# Supply.net
KiCad netlist of a schematic drawn in Altium Designer
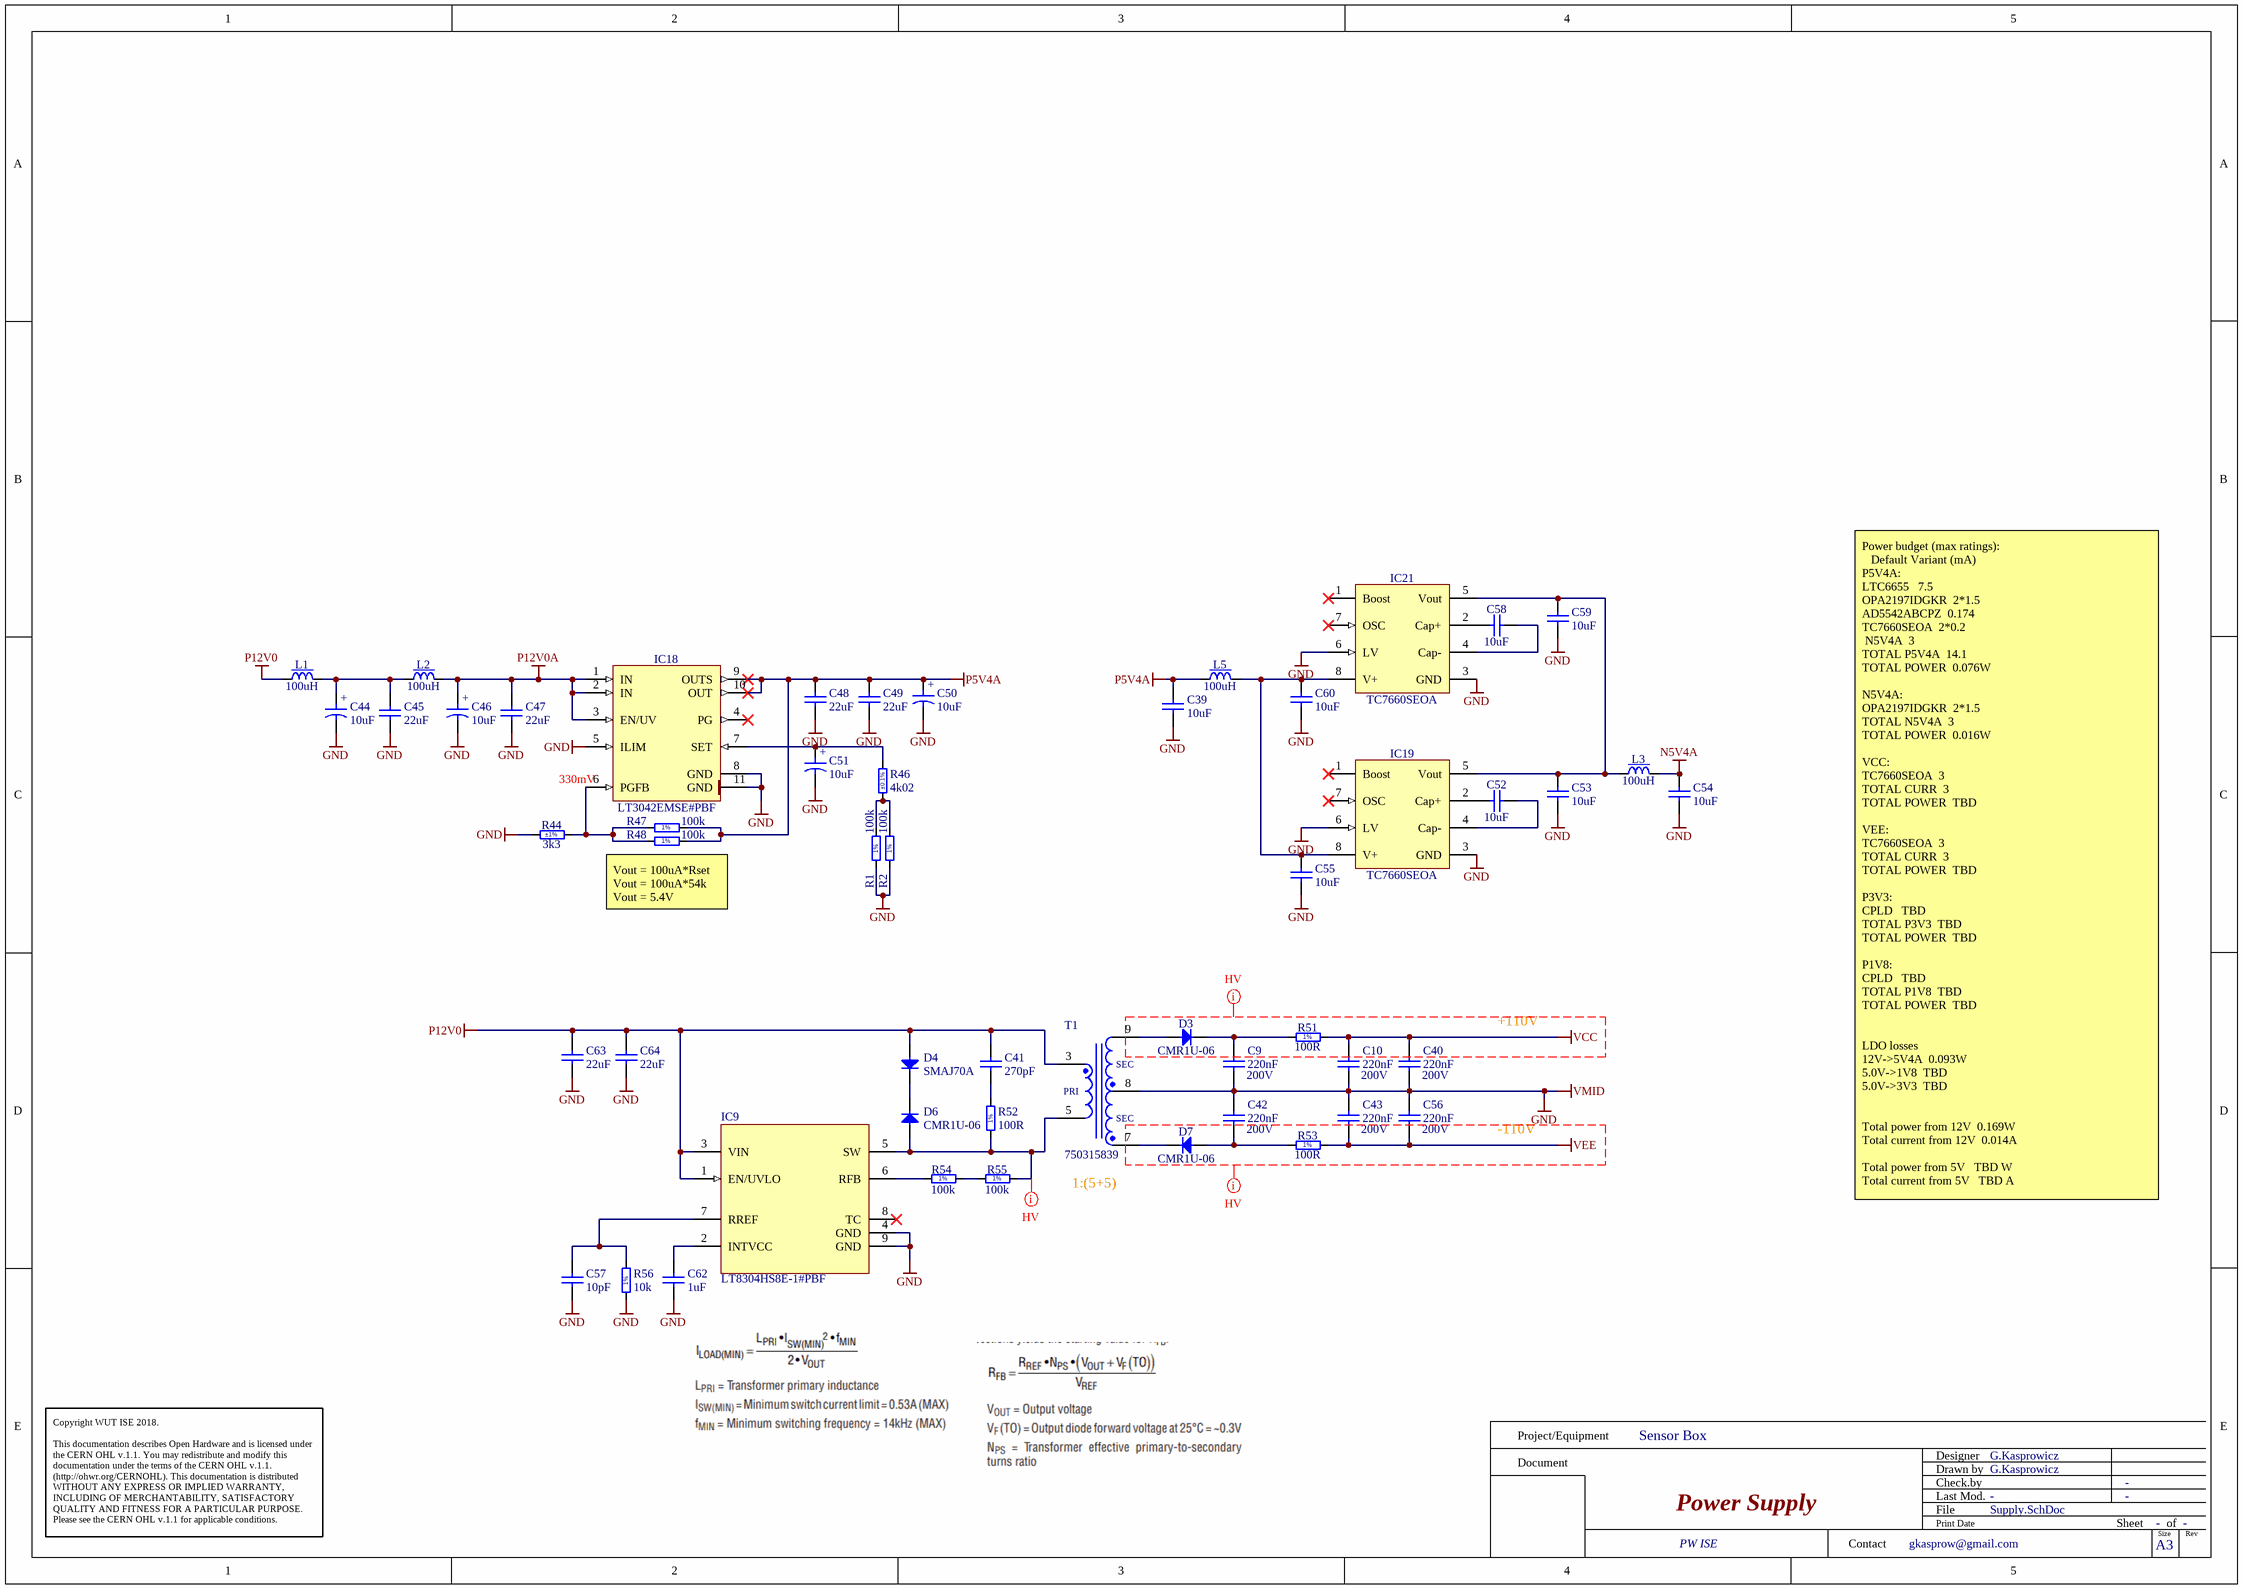
[diagram p0: Supply.SchDoc]

(export (version "E")
  (design (tool "Eeschema 10.0.6"))
  (components
    (comp (ref "C9")
      (value "220nF")
      (footprint "CAPC3216X140N")
      (description "Non-polarised capacitor")
      (fields
        (field (name "PART NUMBER") "CC1206_220NF_250V_10%_X7R")
        (field (name "TOLERANCE") "±10%")
        (field (name "VOLTAGE") "200V")
        (field (name "AUTHOR") "CERN DEM JLC")
      )
      (libsource (lib "Sensor-Box_ADHV") (part "CC1206_220NF_250V_10%_X7R"))
    )
    (comp (ref "C10")
      (value "220nF")
      (footprint "CAPC3216X140N")
      (description "Non-polarised capacitor")
      (fields
        (field (name "PART NUMBER") "CC1206_220NF_250V_10%_X7R")
        (field (name "TOLERANCE") "±10%")
        (field (name "VOLTAGE") "200V")
        (field (name "AUTHOR") "CERN DEM JLC")
      )
      (libsource (lib "Sensor-Box_ADHV") (part "CC1206_220NF_250V_10%_X7R"))
    )
    (comp (ref "C39")
      (value "10uF")
      (footprint "CAPC1608X80N")
      (description "Non-polarised capacitor")
      (fields
        (field (name "PART NUMBER") "CC0603_10UF_10V_10%_X5R")
        (field (name "VOLTAGE") "10V")
        (field (name "AUTHOR") "CERN DEM JLC")
      )
      (libsource (lib "Capacitors") (part "Capacitor - non polarized"))
    )
    (comp (ref "C40")
      (value "220nF")
      (footprint "CAPC3216X140N")
      (description "Non-polarised capacitor")
      (fields
        (field (name "PART NUMBER") "CC1206_220NF_250V_10%_X7R")
        (field (name "TOLERANCE") "±10%")
        (field (name "VOLTAGE") "200V")
        (field (name "AUTHOR") "CERN DEM JLC")
      )
      (libsource (lib "Sensor-Box_ADHV") (part "CC1206_220NF_250V_10%_X7R"))
    )
    (comp (ref "C41")
      (value "270pF")
      (footprint "CAPC2013X115N")
      (description "Non-polarised capacitor")
      (fields
        (field (name "PART NUMBER") "CC0805_270PF_100V_5%_C0G")
        (field (name "VOLTAGE") "100V")
        (field (name "AUTHOR") "CERN DEM JLC")
      )
      (libsource (lib "Sensor-Box_ADHV") (part "CC0805_270PF_100V_5%_C0G"))
    )
    (comp (ref "C42")
      (value "220nF")
      (footprint "CAPC3216X140N")
      (description "Non-polarised capacitor")
      (fields
        (field (name "PART NUMBER") "CC1206_220NF_250V_10%_X7R")
        (field (name "TOLERANCE") "±10%")
        (field (name "VOLTAGE") "200V")
        (field (name "AUTHOR") "CERN DEM JLC")
      )
      (libsource (lib "Sensor-Box_ADHV") (part "CC1206_220NF_250V_10%_X7R"))
    )
    (comp (ref "C43")
      (value "220nF")
      (footprint "CAPC3216X140N")
      (description "Non-polarised capacitor")
      (fields
        (field (name "PART NUMBER") "CC1206_220NF_250V_10%_X7R")
        (field (name "TOLERANCE") "±10%")
        (field (name "VOLTAGE") "200V")
        (field (name "AUTHOR") "CERN DEM JLC")
      )
      (libsource (lib "Sensor-Box_ADHV") (part "CC1206_220NF_250V_10%_X7R"))
    )
    (comp (ref "C44")
      (value "10uF")
      (footprint "CAPMP3216X180N")
      (description "Polarised capacitor")
      (fields
        (field (name "PART NUMBER") "CTE3216-18_10UF_16V_20%_AVX_TCJ")
        (field (name "VOLTAGE") "16V")
        (field (name "AUTHOR") "CERN DEM JLC")
      )
      (libsource (lib "Capacitors") (part "Capacitor - polarized"))
    )
    (comp (ref "C45")
      (value "22uF")
      (footprint "CAPC2012X135N")
      (description "Non-polarised capacitor")
      (fields
        (field (name "PART NUMBER") "CC0805_22UF_16V_10%_X5R")
        (field (name "VOLTAGE") "16V")
        (field (name "AUTHOR") "CERN DEM JLC")
      )
      (libsource (lib "Capacitors") (part "Capacitor - non polarized"))
    )
    (comp (ref "C46")
      (value "10uF")
      (footprint "CAPMP3216X180N")
      (description "Polarised capacitor")
      (fields
        (field (name "PART NUMBER") "CTE3216-18_10UF_16V_20%_AVX_TCJ")
        (field (name "VOLTAGE") "16V")
        (field (name "AUTHOR") "CERN DEM JLC")
      )
      (libsource (lib "Capacitors") (part "Capacitor - polarized"))
    )
    (comp (ref "C47")
      (value "22uF")
      (footprint "CAPC2012X135N")
      (description "Non-polarised capacitor")
      (fields
        (field (name "PART NUMBER") "CC0805_22UF_16V_10%_X5R")
        (field (name "VOLTAGE") "16V")
        (field (name "AUTHOR") "CERN DEM JLC")
      )
      (libsource (lib "Capacitors") (part "Capacitor - non polarized"))
    )
    (comp (ref "C48")
      (value "22uF")
      (footprint "CAPC2012X135N")
      (description "Non-polarised capacitor")
      (fields
        (field (name "PART NUMBER") "CC0805_22UF_16V_10%_X5R")
        (field (name "VOLTAGE") "16V")
        (field (name "AUTHOR") "CERN DEM JLC")
      )
      (libsource (lib "Capacitors") (part "Capacitor - non polarized"))
    )
    (comp (ref "C49")
      (value "22uF")
      (footprint "CAPC2012X135N")
      (description "Non-polarised capacitor")
      (fields
        (field (name "PART NUMBER") "CC0805_22UF_16V_10%_X5R")
        (field (name "VOLTAGE") "16V")
        (field (name "AUTHOR") "CERN DEM JLC")
      )
      (libsource (lib "Capacitors") (part "Capacitor - non polarized"))
    )
    (comp (ref "C50")
      (value "10uF")
      (footprint "CAPMP3216X180N")
      (description "Polarised capacitor")
      (fields
        (field (name "PART NUMBER") "CTE3216-18_10UF_16V_20%_AVX_TCJ")
        (field (name "VOLTAGE") "16V")
        (field (name "AUTHOR") "CERN DEM JLC")
      )
      (libsource (lib "Capacitors") (part "Capacitor - polarized"))
    )
    (comp (ref "C51")
      (value "10uF")
      (footprint "CAPMP3216X180N")
      (description "Polarised capacitor")
      (fields
        (field (name "PART NUMBER") "CTE3216-18_10UF_16V_20%_AVX_TCJ")
        (field (name "VOLTAGE") "16V")
        (field (name "AUTHOR") "CERN DEM JLC")
      )
      (libsource (lib "Capacitors") (part "Capacitor - polarized"))
    )
    (comp (ref "C52")
      (value "10uF")
      (footprint "CAPC1608X80N")
      (description "Non-polarised capacitor")
      (fields
        (field (name "PART NUMBER") "CC0603_10UF_10V_10%_X5R")
        (field (name "VOLTAGE") "10V")
        (field (name "AUTHOR") "CERN DEM JLC")
      )
      (libsource (lib "Capacitors") (part "Capacitor - non polarized"))
    )
    (comp (ref "C53")
      (value "10uF")
      (footprint "CAPC1608X80N")
      (description "Non-polarised capacitor")
      (fields
        (field (name "PART NUMBER") "CC0603_10UF_10V_10%_X5R")
        (field (name "VOLTAGE") "10V")
        (field (name "AUTHOR") "CERN DEM JLC")
      )
      (libsource (lib "Capacitors") (part "Capacitor - non polarized"))
    )
    (comp (ref "C54")
      (value "10uF")
      (footprint "CAPC1608X80N")
      (description "Non-polarised capacitor")
      (fields
        (field (name "PART NUMBER") "CC0603_10UF_10V_10%_X5R")
        (field (name "VOLTAGE") "10V")
        (field (name "AUTHOR") "CERN DEM JLC")
      )
      (libsource (lib "Capacitors") (part "Capacitor - non polarized"))
    )
    (comp (ref "C55")
      (value "10uF")
      (footprint "CAPC1608X80N")
      (description "Non-polarised capacitor")
      (fields
        (field (name "PART NUMBER") "CC0603_10UF_10V_10%_X5R")
        (field (name "VOLTAGE") "10V")
        (field (name "AUTHOR") "CERN DEM JLC")
      )
      (libsource (lib "Capacitors") (part "Capacitor - non polarized"))
    )
    (comp (ref "C56")
      (value "220nF")
      (footprint "CAPC3216X140N")
      (description "Non-polarised capacitor")
      (fields
        (field (name "PART NUMBER") "CC1206_220NF_250V_10%_X7R")
        (field (name "TOLERANCE") "±10%")
        (field (name "VOLTAGE") "200V")
        (field (name "AUTHOR") "CERN DEM JLC")
      )
      (libsource (lib "Sensor-Box_ADHV") (part "CC1206_220NF_250V_10%_X7R"))
    )
    (comp (ref "C57")
      (value "10pF")
      (footprint "CAPC1005X55N")
      (description "Non-polarised capacitor")
      (fields
        (field (name "PART NUMBER") "CC0402_10PF_50V_5%_C0G")
        (field (name "VOLTAGE") "50V")
        (field (name "AUTHOR") "CERN DEM JLC")
      )
      (libsource (lib "Sensor-Box_ADHV") (part "CC0402_10PF_50V_5%_C0G"))
    )
    (comp (ref "C58")
      (value "10uF")
      (footprint "CAPC1608X80N")
      (description "Non-polarised capacitor")
      (fields
        (field (name "PART NUMBER") "CC0603_10UF_10V_10%_X5R")
        (field (name "VOLTAGE") "10V")
        (field (name "AUTHOR") "CERN DEM JLC")
      )
      (libsource (lib "Capacitors") (part "Capacitor - non polarized"))
    )
    (comp (ref "C59")
      (value "10uF")
      (footprint "CAPC1608X80N")
      (description "Non-polarised capacitor")
      (fields
        (field (name "PART NUMBER") "CC0603_10UF_10V_10%_X5R")
        (field (name "VOLTAGE") "10V")
        (field (name "AUTHOR") "CERN DEM JLC")
      )
      (libsource (lib "Capacitors") (part "Capacitor - non polarized"))
    )
    (comp (ref "C60")
      (value "10uF")
      (footprint "CAPC1608X80N")
      (description "Non-polarised capacitor")
      (fields
        (field (name "PART NUMBER") "CC0603_10UF_10V_10%_X5R")
        (field (name "VOLTAGE") "10V")
        (field (name "AUTHOR") "CERN DEM JLC")
      )
      (libsource (lib "Capacitors") (part "Capacitor - non polarized"))
    )
    (comp (ref "C62")
      (value "1uF")
      (footprint "CAPC1608X87N")
      (description "Non-polarised capacitor")
      (fields
        (field (name "PART NUMBER") "CC0603_1UF_25V_10%_X7R")
        (field (name "VOLTAGE") "25V")
        (field (name "AUTHOR") "CERN DEM JLC")
      )
      (libsource (lib "Capacitors") (part "Capacitor - non polarized"))
    )
    (comp (ref "C63")
      (value "22uF")
      (footprint "CAPC2012X135N")
      (description "Non-polarised capacitor")
      (fields
        (field (name "PART NUMBER") "CC0805_22UF_16V_10%_X5R")
        (field (name "VOLTAGE") "16V")
        (field (name "AUTHOR") "CERN DEM JLC")
      )
      (libsource (lib "Capacitors") (part "Capacitor - non polarized"))
    )
    (comp (ref "C64")
      (value "22uF")
      (footprint "CAPC2012X135N")
      (description "Non-polarised capacitor")
      (fields
        (field (name "PART NUMBER") "CC0805_22UF_16V_10%_X5R")
        (field (name "VOLTAGE") "16V")
        (field (name "AUTHOR") "CERN DEM JLC")
      )
      (libsource (lib "Capacitors") (part "Capacitor - non polarized"))
    )
    (comp (ref "D3")
      (value "CMR1U-06")
      (footprint "FP-SMA-MFG")
      (description "Diode")
      (fields
        (field (name "VOLTAGE") "600V")
        (field (name "MANUFACTURER") "Central Semiconductor")
        (field (name "AUTHOR") "CERN DEM JLC")
      )
      (libsource (lib "Sensor-Box_ADHV") (part "CMR1U-06"))
    )
    (comp (ref "D4")
      (value "SMAJ70A")
      (footprint "FP-SMA-MFG")
      (description "Diode")
      (fields
        (field (name "VOLTAGE") "70V")
        (field (name "POWER") "400W")
        (field (name "AUTHOR") "CERN DEM JLC")
      )
      (libsource (lib "Sensor-Box_ADHV") (part "SMAJ70A"))
    )
    (comp (ref "D6")
      (value "CMR1U-06")
      (footprint "FP-SMA-MFG")
      (description "Diode")
      (fields
        (field (name "VOLTAGE") "600V")
        (field (name "MANUFACTURER") "Central Semiconductor")
        (field (name "AUTHOR") "CERN DEM JLC")
      )
      (libsource (lib "Sensor-Box_ADHV") (part "CMR1U-06"))
    )
    (comp (ref "D7")
      (value "CMR1U-06")
      (footprint "FP-SMA-MFG")
      (description "Diode")
      (fields
        (field (name "VOLTAGE") "600V")
        (field (name "MANUFACTURER") "Central Semiconductor")
        (field (name "AUTHOR") "CERN DEM JLC")
      )
      (libsource (lib "Sensor-Box_ADHV") (part "CMR1U-06"))
    )
    (comp (ref "IC9")
      (value "LT8304HS8E-1#PBF")
      (footprint "FP-S8E-8-05-08-1857-MFG")
      (description "IC REG FLYBACK ADJ 2A 8SOIC")
      (fields (field (name "MANUFACTURER") "Analog Devices"))
      (libsource (lib "Sensor-Box_ADHV") (part "LT8304HS8E-1#PBF"))
    )
    (comp (ref "IC18")
      (value "LT3042EMSE#PBF")
      (footprint "SOP50P490X110-11N-R168X198")
      (description "20V, 200mA, Ultralow Noise, Ultrahigh PSRR RF Linear Regulator")
      (fields (field (name "MANUFACTURER") "LINEAR TECHNOLOGY") (field (name "AUTHOR") "CERN DEM MR"))
      (libsource (lib "ICs And Semiconductors") (part "LT3042"))
    )
    (comp (ref "IC19")
      (value "TC7660SEOA")
      (footprint "SOIC127P600X175-8N")
      (description "Super Charge Pump DC-to-DC Voltage Converter")
      (fields (field (name "MANUFACTURER") "MICROCHIP TECHNOLOGY") (field (name "AUTHOR") "CERN DEM HF"))
      (libsource (lib "ICs And Semiconductors") (part "TC7660S"))
    )
    (comp (ref "IC21")
      (value "TC7660SEOA")
      (footprint "SOIC127P600X175-8N")
      (description "Super Charge Pump DC-to-DC Voltage Converter")
      (fields (field (name "MANUFACTURER") "MICROCHIP TECHNOLOGY") (field (name "AUTHOR") "CERN DEM HF"))
      (libsource (lib "ICs And Semiconductors") (part "TC7660S"))
    )
    (comp (ref "L1")
      (value "100uH")
      (footprint "INDM5650X530N")
      (description "Inductor With Core")
      (fields
        (field (name "PART NUMBER") "IND2220_100UH_10%_EPCOS_B82442H")
        (field (name "POWER") "350mA")
        (field (name "AUTHOR") "CERN DEM JLC")
      )
      (libsource (lib "Inductors & Transformers") (part "Inductor With Magnetic core"))
    )
    (comp (ref "L2")
      (value "100uH")
      (footprint "INDM5650X530N")
      (description "Inductor With Core")
      (fields
        (field (name "PART NUMBER") "IND2220_100UH_10%_EPCOS_B82442H")
        (field (name "POWER") "350mA")
        (field (name "AUTHOR") "CERN DEM JLC")
      )
      (libsource (lib "Inductors & Transformers") (part "Inductor With Magnetic core"))
    )
    (comp (ref "L3")
      (value "100uH")
      (footprint "INDM3225X240N")
      (description "Inductor With Core")
      (fields
        (field (name "PART NUMBER") "IND1210_100UH_10%_EPCOS_B82422H")
        (field (name "POWER") "150mA")
        (field (name "AUTHOR") "CERN DEM JLC")
      )
      (libsource (lib "Inductors & Transformers") (part "Inductor With Magnetic core"))
    )
    (comp (ref "L5")
      (value "100uH")
      (footprint "INDM3225X240N")
      (description "Inductor With Core")
      (fields
        (field (name "PART NUMBER") "IND1210_100UH_10%_EPCOS_B82422H")
        (field (name "POWER") "150mA")
        (field (name "AUTHOR") "CERN DEM JLC")
      )
      (libsource (lib "Inductors & Transformers") (part "Inductor With Magnetic core"))
    )
    (comp (ref "R1")
      (value "100k")
      (footprint "RESC1005X40N")
      (description "Resistor - 1%")
      (fields
        (field (name "PART NUMBER") "R0402_100K_1%_0.0625W_100PPM")
        (field (name "MANUFACTURER") "GENERIC")
        (field (name "AUTHOR") "CERN DEM JLC")
      )
      (libsource (lib "Resistors") (part "Resistor - 1%"))
    )
    (comp (ref "R2")
      (value "100k")
      (footprint "RESC1005X40N")
      (description "Resistor - 1%")
      (fields
        (field (name "PART NUMBER") "R0402_100K_1%_0.0625W_100PPM")
        (field (name "MANUFACTURER") "GENERIC")
        (field (name "AUTHOR") "CERN DEM JLC")
      )
      (libsource (lib "Resistors") (part "Resistor - 1%"))
    )
    (comp (ref "R44")
      (value "3k3")
      (footprint "RESC1005X40N")
      (description "Resistor - 1%")
      (fields
        (field (name "TOLERANCE") "±1%")
        (field (name "PART NUMBER") "R0402_3K3_1%_0.0625W_100PPM")
        (field (name "POWER") "0.0625W")
        (field (name "AUTHOR") "CERN DEM JLC")
      )
      (libsource (lib "Resistors") (part "Resistor - 1%"))
    )
    (comp (ref "R46")
      (value "4k02")
      (footprint "RESC1608X55N")
      (description "Resistor - 0.1%")
      (fields
        (field (name "PART NUMBER") "R0603_4K02_0.1%_0.063W_10PPM")
        (field (name "POWER") "0.063W")
        (field (name "TOLERANCE") "±0.1%")
        (field (name "AUTHOR") "CERN DEM BC")
      )
      (libsource (lib "Sensor-Box_Piezo_Driver") (part "R0603_4K02_0.1%_0.063W_10PPM_1"))
    )
    (comp (ref "R47")
      (value "100k")
      (footprint "RESC1005X40N")
      (description "Resistor - 1%")
      (fields
        (field (name "PART NUMBER") "R0402_100K_1%_0.0625W_100PPM")
        (field (name "MANUFACTURER") "GENERIC")
        (field (name "AUTHOR") "CERN DEM JLC")
      )
      (libsource (lib "Resistors") (part "Resistor - 1%"))
    )
    (comp (ref "R48")
      (value "100k")
      (footprint "RESC1005X40N")
      (description "Resistor - 1%")
      (fields
        (field (name "PART NUMBER") "R0402_100K_1%_0.0625W_100PPM")
        (field (name "MANUFACTURER") "GENERIC")
        (field (name "AUTHOR") "CERN DEM JLC")
      )
      (libsource (lib "Resistors") (part "Resistor - 1%"))
    )
    (comp (ref "R51")
      (value "100R")
      (footprint "RESC3216X65N")
      (description "Resistor - 1%")
      (fields
        (field (name "PART NUMBER") "R1206_100R_1%_0.5W_100PPM")
        (field (name "POWER") "0.5W")
        (field (name "AUTHOR") "CERN DEM JLC")
      )
      (libsource (lib "Sensor-Box_ADHV") (part "R1206_100R_1%_0.5W_100PPM"))
    )
    (comp (ref "R52")
      (value "100R")
      (footprint "RESC3216X65N")
      (description "Resistor - 1%")
      (fields
        (field (name "PART NUMBER") "R1206_100R_1%_0.5W_100PPM")
        (field (name "POWER") "0.5W")
        (field (name "AUTHOR") "CERN DEM JLC")
      )
      (libsource (lib "Sensor-Box_ADHV") (part "R1206_100R_1%_0.5W_100PPM"))
    )
    (comp (ref "R53")
      (value "100R")
      (footprint "RESC3216X65N")
      (description "Resistor - 1%")
      (fields
        (field (name "PART NUMBER") "R1206_100R_1%_0.5W_100PPM")
        (field (name "POWER") "0.5W")
        (field (name "AUTHOR") "CERN DEM JLC")
      )
      (libsource (lib "Sensor-Box_ADHV") (part "R1206_100R_1%_0.5W_100PPM"))
    )
    (comp (ref "R54")
      (value "100k")
      (footprint "RESC1005X40N")
      (description "Resistor - 1%")
      (fields
        (field (name "PART NUMBER") "R0402_100K_1%_0.0625W_100PPM")
        (field (name "MANUFACTURER") "GENERIC")
        (field (name "AUTHOR") "CERN DEM JLC")
      )
      (libsource (lib "Resistors") (part "Resistor - 1%"))
    )
    (comp (ref "R55")
      (value "100k")
      (footprint "RESC1005X40N")
      (description "Resistor - 1%")
      (fields
        (field (name "PART NUMBER") "R0402_100K_1%_0.0625W_100PPM")
        (field (name "MANUFACTURER") "GENERIC")
        (field (name "AUTHOR") "CERN DEM JLC")
      )
      (libsource (lib "Resistors") (part "Resistor - 1%"))
    )
    (comp (ref "R56")
      (value "10k")
      (footprint "RESC1005X40N")
      (description "Resistor - 1%")
      (fields
        (field (name "PART NUMBER") "R0402_10K_1%_0.0625W_100PPM")
        (field (name "POWER") "0.0625W")
        (field (name "AUTHOR") "CERN DEM JLC")
      )
      (libsource (lib "Resistors") (part "Resistor - 1%"))
    )
    (comp (ref "T1")
      (value "750315839")
      (footprint "WE-FLYLT_EP13_L13.46W17.75H12.70")
      (description "750315839 Flyback Transformer EP13 SMT; Ui")
      (fields (field (name "MANUFACTURER") "Wurth Elektronik"))
      (libsource (lib "Sensor-Box_ADHV") (part "750315839"))
    )
  )
  (nets
    (net (code "1") (name "GND") (class "Default")
      (node (ref "C10") (pin "1") (pinfunction "1_1") (pintype "passive"))
      (node (ref "C39") (pin "1") (pinfunction "1_1") (pintype "passive"))
      (node (ref "C40") (pin "1") (pinfunction "1_1") (pintype "passive"))
      (node (ref "C42") (pin "2") (pinfunction "2_2") (pintype "passive"))
      (node (ref "C43") (pin "2") (pinfunction "2_2") (pintype "passive"))
      (node (ref "C44") (pin "2") (pinfunction "2_2") (pintype "passive"))
      (node (ref "C45") (pin "1") (pinfunction "1_1") (pintype "passive"))
      (node (ref "C46") (pin "2") (pinfunction "2_2") (pintype "passive"))
      (node (ref "C47") (pin "1") (pinfunction "1_1") (pintype "passive"))
      (node (ref "C48") (pin "1") (pinfunction "1_1") (pintype "passive"))
      (node (ref "C49") (pin "1") (pinfunction "1_1") (pintype "passive"))
      (node (ref "C50") (pin "2") (pinfunction "2_2") (pintype "passive"))
      (node (ref "C51") (pin "2") (pinfunction "2_2") (pintype "passive"))
      (node (ref "C53") (pin "1") (pinfunction "1_1") (pintype "passive"))
      (node (ref "C54") (pin "1") (pinfunction "1_1") (pintype "passive"))
      (node (ref "C55") (pin "1") (pinfunction "1_1") (pintype "passive"))
      (node (ref "C56") (pin "2") (pinfunction "2_2") (pintype "passive"))
      (node (ref "C57") (pin "1") (pinfunction "1_1") (pintype "passive"))
      (node (ref "C59") (pin "1") (pinfunction "1_1") (pintype "passive"))
      (node (ref "C60") (pin "1") (pinfunction "1_1") (pintype "passive"))
      (node (ref "C62") (pin "1") (pinfunction "1_1") (pintype "passive"))
      (node (ref "C63") (pin "1") (pinfunction "1_1") (pintype "passive"))
      (node (ref "C64") (pin "1") (pinfunction "1_1") (pintype "passive"))
      (node (ref "C9") (pin "1") (pinfunction "1_1") (pintype "passive"))
      (node (ref "IC18") (pin "11") (pinfunction "GND_11") (pintype "power_in"))
      (node (ref "IC18") (pin "5") (pinfunction "ILIM_5") (pintype "input"))
      (node (ref "IC18") (pin "8") (pinfunction "GND_8") (pintype "power_in"))
      (node (ref "IC19") (pin "3") (pinfunction "GND_3") (pintype "power_in"))
      (node (ref "IC19") (pin "6") (pinfunction "LV_6") (pintype "input"))
      (node (ref "IC21") (pin "3") (pinfunction "GND_3") (pintype "power_in"))
      (node (ref "IC21") (pin "6") (pinfunction "LV_6") (pintype "input"))
      (node (ref "IC9") (pin "4") (pinfunction "GND_4") (pintype "power_in"))
      (node (ref "IC9") (pin "9") (pinfunction "GND_9") (pintype "power_in"))
      (node (ref "R1") (pin "2") (pinfunction "2_2") (pintype "passive"))
      (node (ref "R2") (pin "2") (pinfunction "2_2") (pintype "passive"))
      (node (ref "R44") (pin "2") (pinfunction "2_2") (pintype "passive"))
      (node (ref "R56") (pin "1") (pinfunction "1_1") (pintype "passive"))
      (node (ref "T1") (pin "8") (pinfunction "8_8") (pintype "passive"))
    )
    (net (code "2") (name "N5V4A") (class "Default")
      (node (ref "C54") (pin "2") (pinfunction "2_2") (pintype "passive"))
      (node (ref "L3") (pin "2") (pinfunction "2_2") (pintype "passive"))
    )
    (net (code "3") (name "Net-(C41-Pad1)") (class "Default")
      (node (ref "C41") (pin "1") (pinfunction "1_1") (pintype "passive"))
      (node (ref "R52") (pin "2") (pinfunction "2_2") (pintype "passive"))
    )
    (net (code "4") (name "Net-(C44-Pad1)") (class "Default")
      (node (ref "C44") (pin "1") (pinfunction "1_1") (pintype "passive"))
      (node (ref "C45") (pin "2") (pinfunction "2_2") (pintype "passive"))
      (node (ref "L1") (pin "2") (pinfunction "2_2") (pintype "passive"))
      (node (ref "L2") (pin "1") (pinfunction "1_1") (pintype "passive"))
    )
    (net (code "5") (name "Net-(D3-A)") (class "Default")
      (node (ref "D3") (pin "2") (pinfunction "A_2") (pintype "passive"))
      (node (ref "T1") (pin "9") (pinfunction "9_9") (pintype "passive"))
    )
    (net (code "6") (name "Net-(D3-C)") (class "Default")
      (node (ref "C9") (pin "2") (pinfunction "2_2") (pintype "passive"))
      (node (ref "D3") (pin "1") (pinfunction "C_1") (pintype "passive"))
      (node (ref "R51") (pin "1") (pinfunction "1_1") (pintype "passive"))
    )
    (net (code "7") (name "Net-(D4-C)") (class "Default")
      (node (ref "D4") (pin "1") (pinfunction "C_1") (pintype "passive"))
      (node (ref "D6") (pin "1") (pinfunction "C_1") (pintype "passive"))
    )
    (net (code "8") (name "Net-(D6-A)") (class "Default")
      (node (ref "D6") (pin "2") (pinfunction "A_2") (pintype "passive"))
      (node (ref "IC9") (pin "5") (pinfunction "SW_5") (pintype "passive"))
      (node (ref "R52") (pin "1") (pinfunction "1_1") (pintype "passive"))
      (node (ref "R55") (pin "1") (pinfunction "1_1") (pintype "passive"))
      (node (ref "T1") (pin "5") (pinfunction "5_5") (pintype "passive"))
    )
    (net (code "9") (name "Net-(D7-A)") (class "Default")
      (node (ref "C42") (pin "1") (pinfunction "1_1") (pintype "passive"))
      (node (ref "D7") (pin "2") (pinfunction "A_2") (pintype "passive"))
      (node (ref "R53") (pin "1") (pinfunction "1_1") (pintype "passive"))
    )
    (net (code "10") (name "Net-(D7-C)") (class "Default")
      (node (ref "D7") (pin "1") (pinfunction "C_1") (pintype "passive"))
      (node (ref "T1") (pin "7") (pinfunction "7_7") (pintype "passive"))
    )
    (net (code "11") (name "Net-(IC9-INTVCC)") (class "Default")
      (node (ref "C62") (pin "2") (pinfunction "2_2") (pintype "passive"))
      (node (ref "IC9") (pin "2") (pinfunction "INTVCC_2") (pintype "power_in"))
    )
    (net (code "12") (name "Net-(IC9-RFB)") (class "Default")
      (node (ref "IC9") (pin "6") (pinfunction "RFB_6") (pintype "passive"))
      (node (ref "R54") (pin "2") (pinfunction "2_2") (pintype "passive"))
    )
    (net (code "13") (name "Net-(IC9-RREF)") (class "Default")
      (node (ref "C57") (pin "2") (pinfunction "2_2") (pintype "passive"))
      (node (ref "IC9") (pin "7") (pinfunction "RREF_7") (pintype "passive"))
      (node (ref "R56") (pin "2") (pinfunction "2_2") (pintype "passive"))
    )
    (net (code "14") (name "Net-(IC18-PGFB)") (class "Default")
      (node (ref "IC18") (pin "6") (pinfunction "PGFB_6") (pintype "input"))
      (node (ref "R44") (pin "1") (pinfunction "1_1") (pintype "passive"))
      (node (ref "R47") (pin "2") (pinfunction "2_2") (pintype "passive"))
      (node (ref "R48") (pin "2") (pinfunction "2_2") (pintype "passive"))
    )
    (net (code "15") (name "Net-(IC18-SET)") (class "Default")
      (node (ref "C51") (pin "1") (pinfunction "1_1") (pintype "passive"))
      (node (ref "IC18") (pin "7") (pinfunction "SET_7") (pintype "input"))
      (node (ref "R46") (pin "2") (pinfunction "2_2") (pintype "passive"))
    )
    (net (code "16") (name "Net-(IC19-Cap+)") (class "Default")
      (node (ref "C52") (pin "1") (pinfunction "1_1") (pintype "passive"))
      (node (ref "IC19") (pin "2") (pinfunction "Cap+_2") (pintype "passive"))
    )
    (net (code "17") (name "Net-(IC19-Cap-)") (class "Default")
      (node (ref "C52") (pin "2") (pinfunction "2_2") (pintype "passive"))
      (node (ref "IC19") (pin "4") (pinfunction "Cap-_4") (pintype "passive"))
    )
    (net (code "18") (name "Net-(IC19-V+)") (class "Default")
      (node (ref "C55") (pin "2") (pinfunction "2_2") (pintype "passive"))
      (node (ref "C60") (pin "2") (pinfunction "2_2") (pintype "passive"))
      (node (ref "IC19") (pin "8") (pinfunction "V+_8") (pintype "power_in"))
      (node (ref "IC21") (pin "8") (pinfunction "V+_8") (pintype "power_in"))
      (node (ref "L5") (pin "2") (pinfunction "2_2") (pintype "passive"))
    )
    (net (code "19") (name "Net-(IC19-Vout)") (class "Default")
      (node (ref "C53") (pin "2") (pinfunction "2_2") (pintype "passive"))
      (node (ref "C59") (pin "2") (pinfunction "2_2") (pintype "passive"))
      (node (ref "IC19") (pin "5") (pinfunction "Vout_5") (pintype "power_in"))
      (node (ref "IC21") (pin "5") (pinfunction "Vout_5") (pintype "power_in"))
      (node (ref "L3") (pin "1") (pinfunction "1_1") (pintype "passive"))
    )
    (net (code "20") (name "Net-(IC21-Cap+)") (class "Default")
      (node (ref "C58") (pin "1") (pinfunction "1_1") (pintype "passive"))
      (node (ref "IC21") (pin "2") (pinfunction "Cap+_2") (pintype "passive"))
    )
    (net (code "21") (name "Net-(IC21-Cap-)") (class "Default")
      (node (ref "C58") (pin "2") (pinfunction "2_2") (pintype "passive"))
      (node (ref "IC21") (pin "4") (pinfunction "Cap-_4") (pintype "passive"))
    )
    (net (code "22") (name "Net-(R1-Pad1)") (class "Default")
      (node (ref "R1") (pin "1") (pinfunction "1_1") (pintype "passive"))
      (node (ref "R2") (pin "1") (pinfunction "1_1") (pintype "passive"))
      (node (ref "R46") (pin "1") (pinfunction "1_1") (pintype "passive"))
    )
    (net (code "23") (name "Net-(R54-Pad1)") (class "Default")
      (node (ref "R54") (pin "1") (pinfunction "1_1") (pintype "passive"))
      (node (ref "R55") (pin "2") (pinfunction "2_2") (pintype "passive"))
    )
    (net (code "24") (name "P5V4A") (class "Default")
      (node (ref "C39") (pin "2") (pinfunction "2_2") (pintype "passive"))
      (node (ref "C48") (pin "2") (pinfunction "2_2") (pintype "passive"))
      (node (ref "C49") (pin "2") (pinfunction "2_2") (pintype "passive"))
      (node (ref "C50") (pin "1") (pinfunction "1_1") (pintype "passive"))
      (node (ref "IC18") (pin "10") (pinfunction "OUT_10") (pintype "output"))
      (node (ref "IC18") (pin "9") (pinfunction "OUTS_9") (pintype "output"))
      (node (ref "L5") (pin "1") (pinfunction "1_1") (pintype "passive"))
      (node (ref "R47") (pin "1") (pinfunction "1_1") (pintype "passive"))
      (node (ref "R48") (pin "1") (pinfunction "1_1") (pintype "passive"))
    )
    (net (code "25") (name "P12V0") (class "Default")
      (node (ref "C41") (pin "2") (pinfunction "2_2") (pintype "passive"))
      (node (ref "C63") (pin "2") (pinfunction "2_2") (pintype "passive"))
      (node (ref "C64") (pin "2") (pinfunction "2_2") (pintype "passive"))
      (node (ref "D4") (pin "2") (pinfunction "A_2") (pintype "passive"))
      (node (ref "IC9") (pin "1") (pinfunction "EN/UVLO_1") (pintype "input"))
      (node (ref "IC9") (pin "3") (pinfunction "VIN_3") (pintype "power_in"))
      (node (ref "L1") (pin "1") (pinfunction "1_1") (pintype "passive"))
      (node (ref "T1") (pin "3") (pinfunction "3_3") (pintype "passive"))
    )
    (net (code "26") (name "P12V0A") (class "Default")
      (node (ref "C46") (pin "1") (pinfunction "1_1") (pintype "passive"))
      (node (ref "C47") (pin "2") (pinfunction "2_2") (pintype "passive"))
      (node (ref "IC18") (pin "1") (pinfunction "IN_1") (pintype "input"))
      (node (ref "IC18") (pin "2") (pinfunction "IN_2") (pintype "input"))
      (node (ref "IC18") (pin "3") (pinfunction "EN/UV_3") (pintype "input"))
      (node (ref "L2") (pin "2") (pinfunction "2_2") (pintype "passive"))
    )
    (net (code "27") (name "VCC") (class "Default")
      (node (ref "C10") (pin "2") (pinfunction "2_2") (pintype "passive"))
      (node (ref "C40") (pin "2") (pinfunction "2_2") (pintype "passive"))
      (node (ref "R51") (pin "2") (pinfunction "2_2") (pintype "passive"))
    )
    (net (code "28") (name "VEE") (class "Default")
      (node (ref "C43") (pin "1") (pinfunction "1_1") (pintype "passive"))
      (node (ref "C56") (pin "1") (pinfunction "1_1") (pintype "passive"))
      (node (ref "R53") (pin "2") (pinfunction "2_2") (pintype "passive"))
    )
    (net (code "29") (name "unconnected-(IC9-TC-Pad8)") (class "Default")
      (node (ref "IC9") (pin "8") (pinfunction "TC_8") (pintype "passive+no_connect"))
    )
    (net (code "30") (name "unconnected-(IC18-PG-Pad4)") (class "Default")
      (node (ref "IC18") (pin "4") (pinfunction "PG_4") (pintype "output+no_connect"))
    )
    (net (code "31") (name "unconnected-(IC19-Boost-Pad1)") (class "Default")
      (node (ref "IC19") (pin "1") (pinfunction "Boost_1") (pintype "passive+no_connect"))
    )
    (net (code "32") (name "unconnected-(IC19-OSC-Pad7)") (class "Default")
      (node (ref "IC19") (pin "7") (pinfunction "OSC_7") (pintype "input+no_connect"))
    )
    (net (code "33") (name "unconnected-(IC21-Boost-Pad1)") (class "Default")
      (node (ref "IC21") (pin "1") (pinfunction "Boost_1") (pintype "passive+no_connect"))
    )
    (net (code "34") (name "unconnected-(IC21-OSC-Pad7)") (class "Default")
      (node (ref "IC21") (pin "7") (pinfunction "OSC_7") (pintype "input+no_connect"))
    )
  )
)
